# power_decoupling.net
KiCad netlist of a schematic drawn in EAGLE
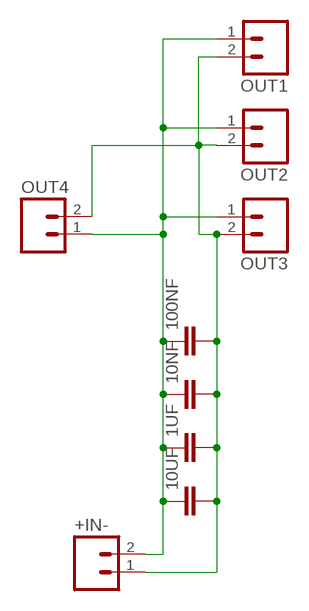
[diagram p0: schematic, sheet 1]

(export (version "E")
  (design (tool "Eeschema 10.0.6"))
  (components
    (comp (ref "+IN-")
      (value "M02PTH")
      (footprint "eagle-import:1X02")
      (libsource (lib "eagle-import") (part "M02PTH"))
    )
    (comp (ref "1UF")
      (value "CAP0805")
      (footprint "eagle-import:0805")
      (libsource (lib "eagle-import") (part "CAP0805"))
    )
    (comp (ref "10NF")
      (value "CAP0805")
      (footprint "eagle-import:0805")
      (libsource (lib "eagle-import") (part "CAP0805"))
    )
    (comp (ref "10UF")
      (value "CAP0805")
      (footprint "eagle-import:0805")
      (libsource (lib "eagle-import") (part "CAP0805"))
    )
    (comp (ref "100NF")
      (value "CAP0805")
      (footprint "eagle-import:0805")
      (libsource (lib "eagle-import") (part "CAP0805"))
    )
    (comp (ref "OUT1")
      (value "M02PTH")
      (footprint "eagle-import:1X02")
      (libsource (lib "eagle-import") (part "M02PTH"))
    )
    (comp (ref "OUT2")
      (value "M02PTH")
      (footprint "eagle-import:1X02")
      (libsource (lib "eagle-import") (part "M02PTH"))
    )
    (comp (ref "OUT3")
      (value "M02PTH")
      (footprint "eagle-import:1X02")
      (libsource (lib "eagle-import") (part "M02PTH"))
    )
    (comp (ref "OUT4")
      (value "M02PTH")
      (footprint "eagle-import:1X02")
      (libsource (lib "eagle-import") (part "M02PTH"))
    )
  )
  (nets
    (net (code "1") (name "Net-(+IN--Pad1)") (class "Default")
      (node (ref "+IN-") (pin "1") (pinfunction "1_1") (pintype "passive"))
      (node (ref "100NF") (pin "2") (pinfunction "2_2") (pintype "passive"))
      (node (ref "10NF") (pin "2") (pinfunction "2_2") (pintype "passive"))
      (node (ref "10UF") (pin "2") (pinfunction "2_2") (pintype "passive"))
      (node (ref "1UF") (pin "2") (pinfunction "2_2") (pintype "passive"))
      (node (ref "OUT1") (pin "2") (pinfunction "2_2") (pintype "passive"))
      (node (ref "OUT2") (pin "2") (pinfunction "2_2") (pintype "passive"))
      (node (ref "OUT3") (pin "2") (pinfunction "2_2") (pintype "passive"))
      (node (ref "OUT4") (pin "2") (pinfunction "2_2") (pintype "passive"))
    )
    (net (code "2") (name "Net-(+IN--Pad2)") (class "Default")
      (node (ref "+IN-") (pin "2") (pinfunction "2_2") (pintype "passive"))
      (node (ref "100NF") (pin "1") (pinfunction "1_1") (pintype "passive"))
      (node (ref "10NF") (pin "1") (pinfunction "1_1") (pintype "passive"))
      (node (ref "10UF") (pin "1") (pinfunction "1_1") (pintype "passive"))
      (node (ref "1UF") (pin "1") (pinfunction "1_1") (pintype "passive"))
      (node (ref "OUT1") (pin "1") (pinfunction "1_1") (pintype "passive"))
      (node (ref "OUT2") (pin "1") (pinfunction "1_1") (pintype "passive"))
      (node (ref "OUT3") (pin "1") (pinfunction "1_1") (pintype "passive"))
      (node (ref "OUT4") (pin "1") (pinfunction "1_1") (pintype "passive"))
    )
  )
)
